# ESP8266_SmartHome_Switch.net
KiCad netlist of a schematic drawn in EAGLE
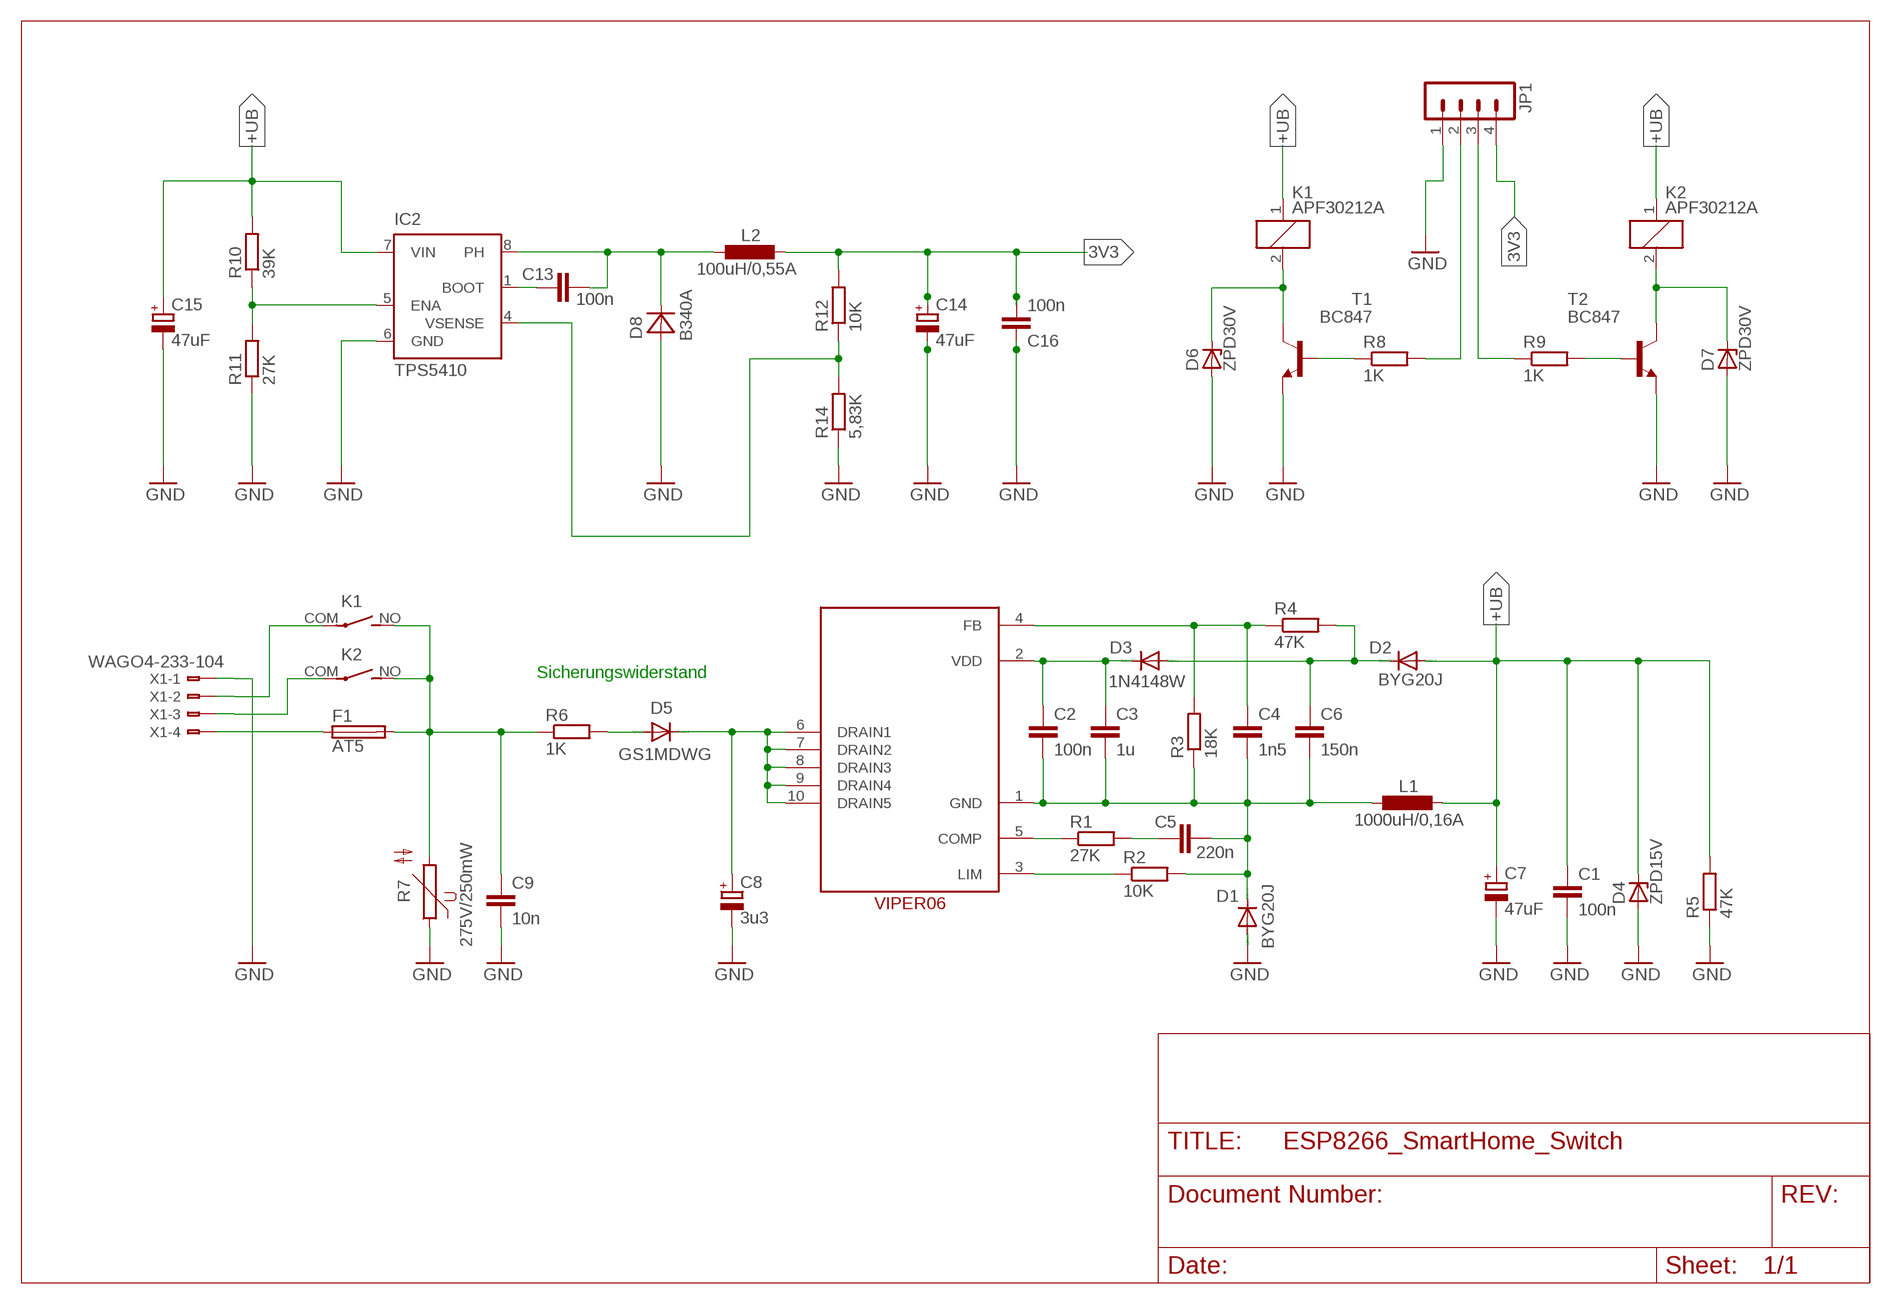
[diagram p0: schematic, sheet 1]

(export (version "E")
  (design (tool "Eeschema 10.0.6"))
  (components
    (comp (ref "C1")
      (value "100n")
      (footprint "eagle-import:C0603")
      (fields (field (name "VOLTAGE") "50V"))
      (libsource (lib "eagle-import") (part "C-EUC0603"))
    )
    (comp (ref "C2")
      (value "100n")
      (footprint "eagle-import:C0603")
      (fields (field (name "VOLTAGE") "50V"))
      (libsource (lib "eagle-import") (part "C-EUC0603"))
    )
    (comp (ref "C3")
      (value "1u")
      (footprint "eagle-import:C0603")
      (fields (field (name "VOLTAGE") "50V"))
      (libsource (lib "eagle-import") (part "C-EUC0603"))
    )
    (comp (ref "C4")
      (value "1n5")
      (footprint "eagle-import:C0603")
      (fields (field (name "VOLTAGE") "25V"))
      (libsource (lib "eagle-import") (part "C-EUC0603"))
    )
    (comp (ref "C5")
      (value "220n")
      (footprint "eagle-import:C0603")
      (fields (field (name "VOLTAGE") "50V"))
      (libsource (lib "eagle-import") (part "C-EUC0603"))
    )
    (comp (ref "C6")
      (value "150n")
      (footprint "eagle-import:C0603")
      (fields (field (name "VOLTAGE") "50V"))
      (libsource (lib "eagle-import") (part "C-EUC0603"))
    )
    (comp (ref "C7")
      (value "47uF")
      (footprint "eagle-import:D_7343-31W")
      (fields (field (name "PARTNUMBER") "T495X476K035ATE200") (field (name "VOLTAGE") "35V"))
      (libsource (lib "eagle-import") (part "CPOL-EUD/7343-31W"))
    )
    (comp (ref "C8")
      (value "3u3")
      (footprint "eagle-import:E5-10,5")
      (fields (field (name "MANUFACTURER") "Wurth") (field (name "PARTNUMBER") "860021375007"))
      (libsource (lib "eagle-import") (part "CPOL-EUE5-10.5"))
    )
    (comp (ref "C9")
      (value "10n")
      (footprint "eagle-import:C7.5B4")
      (fields (field (name "PARTNUMBER") "MKP-X2 10N"))
      (libsource (lib "eagle-import") (part "C7.5/4"))
    )
    (comp (ref "C13")
      (value "100n")
      (footprint "eagle-import:C0603")
      (fields (field (name "VOLTAGE") "50V"))
      (libsource (lib "eagle-import") (part "C-EUC0603"))
    )
    (comp (ref "C14")
      (value "47uF")
      (footprint "eagle-import:D_7343-31W")
      (fields (field (name "PARTNUMBER") "T495X476K035ATE200") (field (name "VOLTAGE") "35V"))
      (libsource (lib "eagle-import") (part "CPOL-EUD/7343-31W"))
    )
    (comp (ref "C15")
      (value "47uF")
      (footprint "eagle-import:D_7343-31W")
      (fields (field (name "PARTNUMBER") "T495X476K035ATE200") (field (name "VOLTAGE") "35V"))
      (libsource (lib "eagle-import") (part "CPOL-EUD/7343-31W"))
    )
    (comp (ref "C16")
      (value "100n")
      (footprint "eagle-import:C0603")
      (fields (field (name "VOLTAGE") "50V"))
      (libsource (lib "eagle-import") (part "C-EUC0603"))
    )
    (comp (ref "D1")
      (value "BYG20J")
      (footprint "eagle-import:DO-214AC")
      (libsource (lib "eagle-import") (part "DIODE-DO-214AC"))
    )
    (comp (ref "D2")
      (value "BYG20J")
      (footprint "eagle-import:DO-214AC")
      (libsource (lib "eagle-import") (part "DIODE-DO-214AC"))
    )
    (comp (ref "D3")
      (value "1N4148W")
      (footprint "eagle-import:SOD-123_MINI-SMA")
      (libsource (lib "eagle-import") (part "CGRM400-G1"))
    )
    (comp (ref "D4")
      (value "ZPD15V")
      (footprint "eagle-import:SMB")
      (libsource (lib "eagle-import") (part "ZENER-DIODESMB"))
    )
    (comp (ref "D5")
      (value "GS1MDWG")
      (footprint "eagle-import:DO214AC")
      (libsource (lib "eagle-import") (part "DIODE-DO214AC"))
    )
    (comp (ref "D6")
      (value "ZPD30V")
      (footprint "eagle-import:SMB")
      (libsource (lib "eagle-import") (part "ZENER-DIODESMB"))
    )
    (comp (ref "D7")
      (value "ZPD30V")
      (footprint "eagle-import:SMB")
      (libsource (lib "eagle-import") (part "ZENER-DIODESMB"))
    )
    (comp (ref "D8")
      (value "B340A")
      (footprint "eagle-import:SMA")
      (libsource (lib "eagle-import") (part "MBRA340T3"))
    )
    (comp (ref "F1")
      (value "AT5")
      (footprint "eagle-import:TR5")
      (libsource (lib "eagle-import") (part "TR5"))
    )
    (comp (ref "IC1")
      (value "VIPER06HS")
      (footprint "eagle-import:SSO10")
      (libsource (lib "eagle-import") (part "VIPER06HS"))
    )
    (comp (ref "IC2")
      (value "TPS5410")
      (footprint "eagle-import:D_R-PDSO-G08")
      (fields (field (name "MPN") "TPS5410DR"))
      (libsource (lib "eagle-import") (part "TPS5410"))
    )
    (comp (ref "JP1")
      (value "MA04-1")
      (footprint "eagle-import:MA04-1")
      (libsource (lib "eagle-import") (part "MA04-1"))
    )
    (comp (ref "K1")
      (value "APF30212A")
      (footprint "eagle-import:APF30212A")
      (libsource (lib "eagle-import") (part "APF30212A"))
    )
    (comp (ref "K2")
      (value "APF30212A")
      (footprint "eagle-import:APF30212A")
      (libsource (lib "eagle-import") (part "APF30212A"))
    )
    (comp (ref "L1")
      (value "1000uH/0,16A")
      (footprint "eagle-import:POWER-CHOKE_WE-TPC")
      (fields (field (name "PARTNUMBER") "744062102"))
      (libsource (lib "eagle-import") (part "L-EUWE-TPC"))
    )
    (comp (ref "L2")
      (value "100uH/0,55A")
      (footprint "eagle-import:POWER-CHOKE_WE-TPC")
      (fields (field (name "PARTNUMBER") "744062101"))
      (libsource (lib "eagle-import") (part "L-EUWE-TPC"))
    )
    (comp (ref "R1")
      (value "27K")
      (footprint "eagle-import:R0603")
      (libsource (lib "eagle-import") (part "resistor_R-EU_R0603"))
    )
    (comp (ref "R2")
      (value "10K")
      (footprint "eagle-import:R0603")
      (libsource (lib "eagle-import") (part "resistor_R-EU_R0603"))
    )
    (comp (ref "R3")
      (value "18K")
      (footprint "eagle-import:R0603")
      (libsource (lib "eagle-import") (part "resistor_R-EU_R0603"))
    )
    (comp (ref "R4")
      (value "47K")
      (footprint "eagle-import:R0603")
      (libsource (lib "eagle-import") (part "resistor_R-EU_R0603"))
    )
    (comp (ref "R5")
      (value "47K")
      (footprint "eagle-import:R0603")
      (libsource (lib "eagle-import") (part "resistor_R-EU_R0603"))
    )
    (comp (ref "R6")
      (value "1K")
      (footprint "eagle-import:0414V")
      (fields (field (name "POWER") "0.5W"))
      (libsource (lib "eagle-import") (part "R-EU_0414/5V"))
    )
    (comp (ref "R7")
      (value "275V/250mW")
      (footprint "eagle-import:S07K275")
      (libsource (lib "eagle-import") (part "S07K275"))
    )
    (comp (ref "R8")
      (value "1K")
      (footprint "eagle-import:R0603")
      (libsource (lib "eagle-import") (part "resistor_R-EU_R0603"))
    )
    (comp (ref "R9")
      (value "1K")
      (footprint "eagle-import:R0603")
      (libsource (lib "eagle-import") (part "resistor_R-EU_R0603"))
    )
    (comp (ref "R10")
      (value "39K")
      (footprint "eagle-import:R0603")
      (libsource (lib "eagle-import") (part "resistor_R-EU_R0603"))
    )
    (comp (ref "R11")
      (value "27K")
      (footprint "eagle-import:R0603")
      (libsource (lib "eagle-import") (part "resistor_R-EU_R0603"))
    )
    (comp (ref "R12")
      (value "10K")
      (footprint "eagle-import:R0603")
      (libsource (lib "eagle-import") (part "resistor_R-EU_R0603"))
    )
    (comp (ref "R14")
      (value "5,83K")
      (footprint "eagle-import:R0603")
      (libsource (lib "eagle-import") (part "resistor_R-EU_R0603"))
    )
    (comp (ref "T1")
      (value "BC847")
      (footprint "eagle-import:SOT23")
      (libsource (lib "eagle-import") (part "BC847"))
    )
    (comp (ref "T2")
      (value "BC847")
      (footprint "eagle-import:SOT23")
      (libsource (lib "eagle-import") (part "BC847"))
    )
    (comp (ref "X1")
      (value "WAGO4-233-104")
      (footprint "eagle-import:233-104")
      (fields (field (name "MPN") "233-104"))
      (libsource (lib "eagle-import") (part "WAGO4-233-104"))
    )
  )
  (nets
    (net (code "1") (name "+UB") (class "Default")
      (node (ref "C1") (pin "1") (pinfunction "1_1") (pintype "passive"))
      (node (ref "C15") (pin "+") (pinfunction "+_+") (pintype "passive"))
      (node (ref "C7") (pin "+") (pinfunction "+_+") (pintype "passive"))
      (node (ref "D2") (pin "A") (pinfunction "A_A") (pintype "passive"))
      (node (ref "D4") (pin "C") (pinfunction "C_C") (pintype "passive"))
      (node (ref "IC2") (pin "7") (pinfunction "VIN_7") (pintype "input"))
      (node (ref "K1") (pin "1") (pinfunction "1_1") (pintype "passive"))
      (node (ref "K2") (pin "1") (pinfunction "1_1") (pintype "passive"))
      (node (ref "L1") (pin "1") (pinfunction "1_1") (pintype "passive"))
      (node (ref "R10") (pin "2") (pinfunction "2_2") (pintype "passive"))
      (node (ref "R5") (pin "2") (pinfunction "2_2") (pintype "passive"))
    )
    (net (code "2") (name "3V3") (class "Default")
      (node (ref "C14") (pin "+") (pinfunction "+_+") (pintype "passive"))
      (node (ref "C16") (pin "2") (pinfunction "2_2") (pintype "passive"))
      (node (ref "JP1") (pin "4") (pinfunction "4_4") (pintype "passive"))
      (node (ref "L2") (pin "1") (pinfunction "1_1") (pintype "passive"))
      (node (ref "R12") (pin "2") (pinfunction "2_2") (pintype "passive"))
    )
    (net (code "3") (name "GND") (class "Default")
      (node (ref "C1") (pin "2") (pinfunction "2_2") (pintype "passive"))
      (node (ref "C14") (pin "-") (pinfunction "-_-") (pintype "passive"))
      (node (ref "C15") (pin "-") (pinfunction "-_-") (pintype "passive"))
      (node (ref "C16") (pin "1") (pinfunction "1_1") (pintype "passive"))
      (node (ref "C7") (pin "-") (pinfunction "-_-") (pintype "passive"))
      (node (ref "C8") (pin "-") (pinfunction "-_-") (pintype "passive"))
      (node (ref "C9") (pin "2") (pinfunction "2_2") (pintype "passive"))
      (node (ref "D1") (pin "A") (pinfunction "A_A") (pintype "passive"))
      (node (ref "D4") (pin "A") (pinfunction "A_A") (pintype "passive"))
      (node (ref "D6") (pin "A") (pinfunction "A_A") (pintype "passive"))
      (node (ref "D7") (pin "A") (pinfunction "A_A") (pintype "passive"))
      (node (ref "D8") (pin "A") (pinfunction "A_A") (pintype "passive"))
      (node (ref "IC2") (pin "6") (pinfunction "GND_6") (pintype "power_in"))
      (node (ref "JP1") (pin "1") (pinfunction "1_1") (pintype "passive"))
      (node (ref "R11") (pin "1") (pinfunction "1_1") (pintype "passive"))
      (node (ref "R14") (pin "1") (pinfunction "1_1") (pintype "passive"))
      (node (ref "R5") (pin "1") (pinfunction "1_1") (pintype "passive"))
      (node (ref "R7") (pin "1") (pinfunction "1_1") (pintype "passive"))
      (node (ref "T1") (pin "2") (pinfunction "E_2") (pintype "passive"))
      (node (ref "T2") (pin "2") (pinfunction "E_2") (pintype "passive"))
      (node (ref "X1") (pin "A1") (pinfunction "A1_A1") (pintype "passive"))
      (node (ref "X1") (pin "B1") (pinfunction "B1_B1") (pintype "passive"))
    )
    (net (code "4") (name "Net-(C5-Pad1)") (class "Default")
      (node (ref "C5") (pin "1") (pinfunction "1_1") (pintype "passive"))
      (node (ref "R1") (pin "2") (pinfunction "2_2") (pintype "passive"))
    )
    (net (code "5") (name "Net-(C6-Pad1)") (class "Default")
      (node (ref "C6") (pin "1") (pinfunction "1_1") (pintype "passive"))
      (node (ref "D2") (pin "C") (pinfunction "C_C") (pintype "passive"))
      (node (ref "D3") (pin "A") (pinfunction "A_A") (pintype "passive"))
      (node (ref "R4") (pin "2") (pinfunction "2_2") (pintype "passive"))
    )
    (net (code "6") (name "Net-(D5-PadA)") (class "Default")
      (node (ref "D5") (pin "A") (pinfunction "A_A") (pintype "passive"))
      (node (ref "R6") (pin "2") (pinfunction "2_2") (pintype "passive"))
    )
    (net (code "7") (name "Net-(IC1-COMP)") (class "Default")
      (node (ref "IC1") (pin "5") (pinfunction "COMP_5") (pintype "bidirectional"))
      (node (ref "R1") (pin "1") (pinfunction "1_1") (pintype "passive"))
    )
    (net (code "8") (name "Net-(IC1-DRAIN1)") (class "Default")
      (node (ref "C8") (pin "+") (pinfunction "+_+") (pintype "passive"))
      (node (ref "D5") (pin "C") (pinfunction "C_C") (pintype "passive"))
      (node (ref "IC1") (pin "10") (pinfunction "DRAIN5_10") (pintype "bidirectional"))
      (node (ref "IC1") (pin "6") (pinfunction "DRAIN1_6") (pintype "bidirectional"))
      (node (ref "IC1") (pin "7") (pinfunction "DRAIN2_7") (pintype "bidirectional"))
      (node (ref "IC1") (pin "8") (pinfunction "DRAIN3_8") (pintype "bidirectional"))
      (node (ref "IC1") (pin "9") (pinfunction "DRAIN4_9") (pintype "bidirectional"))
    )
    (net (code "9") (name "Net-(IC1-FB)") (class "Default")
      (node (ref "C4") (pin "1") (pinfunction "1_1") (pintype "passive"))
      (node (ref "IC1") (pin "4") (pinfunction "FB_4") (pintype "input"))
      (node (ref "R3") (pin "2") (pinfunction "2_2") (pintype "passive"))
      (node (ref "R4") (pin "1") (pinfunction "1_1") (pintype "passive"))
    )
    (net (code "10") (name "Net-(IC1-GND)") (class "Default")
      (node (ref "C2") (pin "2") (pinfunction "2_2") (pintype "passive"))
      (node (ref "C3") (pin "2") (pinfunction "2_2") (pintype "passive"))
      (node (ref "C4") (pin "2") (pinfunction "2_2") (pintype "passive"))
      (node (ref "C5") (pin "2") (pinfunction "2_2") (pintype "passive"))
      (node (ref "C6") (pin "2") (pinfunction "2_2") (pintype "passive"))
      (node (ref "D1") (pin "C") (pinfunction "C_C") (pintype "passive"))
      (node (ref "IC1") (pin "1") (pinfunction "GND_1") (pintype "bidirectional"))
      (node (ref "L1") (pin "2") (pinfunction "2_2") (pintype "passive"))
      (node (ref "R2") (pin "2") (pinfunction "2_2") (pintype "passive"))
      (node (ref "R3") (pin "1") (pinfunction "1_1") (pintype "passive"))
    )
    (net (code "11") (name "Net-(IC1-LIM)") (class "Default")
      (node (ref "IC1") (pin "3") (pinfunction "LIM_3") (pintype "bidirectional"))
      (node (ref "R2") (pin "1") (pinfunction "1_1") (pintype "passive"))
    )
    (net (code "12") (name "Net-(IC1-VDD)") (class "Default")
      (node (ref "C2") (pin "1") (pinfunction "1_1") (pintype "passive"))
      (node (ref "C3") (pin "1") (pinfunction "1_1") (pintype "passive"))
      (node (ref "D3") (pin "C") (pinfunction "C_C") (pintype "passive"))
      (node (ref "IC1") (pin "2") (pinfunction "VDD_2") (pintype "bidirectional"))
    )
    (net (code "13") (name "Net-(IC2-BOOT)") (class "Default")
      (node (ref "C13") (pin "1") (pinfunction "1_1") (pintype "passive"))
      (node (ref "IC2") (pin "1") (pinfunction "BOOT_1") (pintype "output"))
    )
    (net (code "14") (name "Net-(IC2-ENA)") (class "Default")
      (node (ref "IC2") (pin "5") (pinfunction "ENA_5") (pintype "input"))
      (node (ref "R10") (pin "1") (pinfunction "1_1") (pintype "passive"))
      (node (ref "R11") (pin "2") (pinfunction "2_2") (pintype "passive"))
    )
    (net (code "15") (name "Net-(IC2-PH)") (class "Default")
      (node (ref "C13") (pin "2") (pinfunction "2_2") (pintype "passive"))
      (node (ref "D8") (pin "C") (pinfunction "C_C") (pintype "passive"))
      (node (ref "IC2") (pin "8") (pinfunction "PH_8") (pintype "output"))
      (node (ref "L2") (pin "2") (pinfunction "2_2") (pintype "passive"))
    )
    (net (code "16") (name "Net-(IC2-VSENSE)") (class "Default")
      (node (ref "IC2") (pin "4") (pinfunction "VSENSE_4") (pintype "input"))
      (node (ref "R12") (pin "1") (pinfunction "1_1") (pintype "passive"))
      (node (ref "R14") (pin "2") (pinfunction "2_2") (pintype "passive"))
    )
    (net (code "17") (name "Net-(JP1-Pad2)") (class "Default")
      (node (ref "JP1") (pin "2") (pinfunction "2_2") (pintype "passive"))
      (node (ref "R8") (pin "2") (pinfunction "2_2") (pintype "passive"))
    )
    (net (code "18") (name "Net-(JP1-Pad3)") (class "Default")
      (node (ref "JP1") (pin "3") (pinfunction "3_3") (pintype "passive"))
      (node (ref "R9") (pin "1") (pinfunction "1_1") (pintype "passive"))
    )
    (net (code "19") (name "Net-(K1B-P)") (class "Default")
      (node (ref "K1") (pin "COM") (pinfunction "P_COM") (pintype "passive"))
      (node (ref "X1") (pin "A2") (pinfunction "A1_A2") (pintype "passive"))
      (node (ref "X1") (pin "B2") (pinfunction "B1_B2") (pintype "passive"))
    )
    (net (code "20") (name "Net-(K1B-S)") (class "Default")
      (node (ref "C9") (pin "1") (pinfunction "1_1") (pintype "passive"))
      (node (ref "F1") (pin "2") (pinfunction "2_2") (pintype "passive"))
      (node (ref "K1") (pin "NO") (pinfunction "S_NO") (pintype "passive"))
      (node (ref "K2") (pin "NO") (pinfunction "S_NO") (pintype "passive"))
      (node (ref "R6") (pin "1") (pinfunction "1_1") (pintype "passive"))
      (node (ref "R7") (pin "2") (pinfunction "2_2") (pintype "passive"))
    )
    (net (code "21") (name "Net-(K2B-P)") (class "Default")
      (node (ref "K2") (pin "COM") (pinfunction "P_COM") (pintype "passive"))
      (node (ref "X1") (pin "A3") (pinfunction "A1_A3") (pintype "passive"))
      (node (ref "X1") (pin "B3") (pinfunction "B1_B3") (pintype "passive"))
    )
    (net (code "22") (name "Net-(T1-B)") (class "Default")
      (node (ref "R8") (pin "1") (pinfunction "1_1") (pintype "passive"))
      (node (ref "T1") (pin "1") (pinfunction "B_1") (pintype "passive"))
    )
    (net (code "23") (name "Net-(T1-C)") (class "Default")
      (node (ref "D6") (pin "C") (pinfunction "C_C") (pintype "passive"))
      (node (ref "K1") (pin "2") (pinfunction "2_2") (pintype "passive"))
      (node (ref "T1") (pin "3") (pinfunction "C_3") (pintype "passive"))
    )
    (net (code "24") (name "Net-(T2-B)") (class "Default")
      (node (ref "R9") (pin "2") (pinfunction "2_2") (pintype "passive"))
      (node (ref "T2") (pin "1") (pinfunction "B_1") (pintype "passive"))
    )
    (net (code "25") (name "Net-(T2-C)") (class "Default")
      (node (ref "D7") (pin "C") (pinfunction "C_C") (pintype "passive"))
      (node (ref "K2") (pin "2") (pinfunction "2_2") (pintype "passive"))
      (node (ref "T2") (pin "3") (pinfunction "C_3") (pintype "passive"))
    )
    (net (code "26") (name "Net-(X1D-A1)") (class "Default")
      (node (ref "F1") (pin "1") (pinfunction "1_1") (pintype "passive"))
      (node (ref "X1") (pin "A4") (pinfunction "A1_A4") (pintype "passive"))
      (node (ref "X1") (pin "B4") (pinfunction "B1_B4") (pintype "passive"))
    )
  )
)
